# MainBoard_Simple.net
KiCad netlist of a schematic drawn in EAGLE
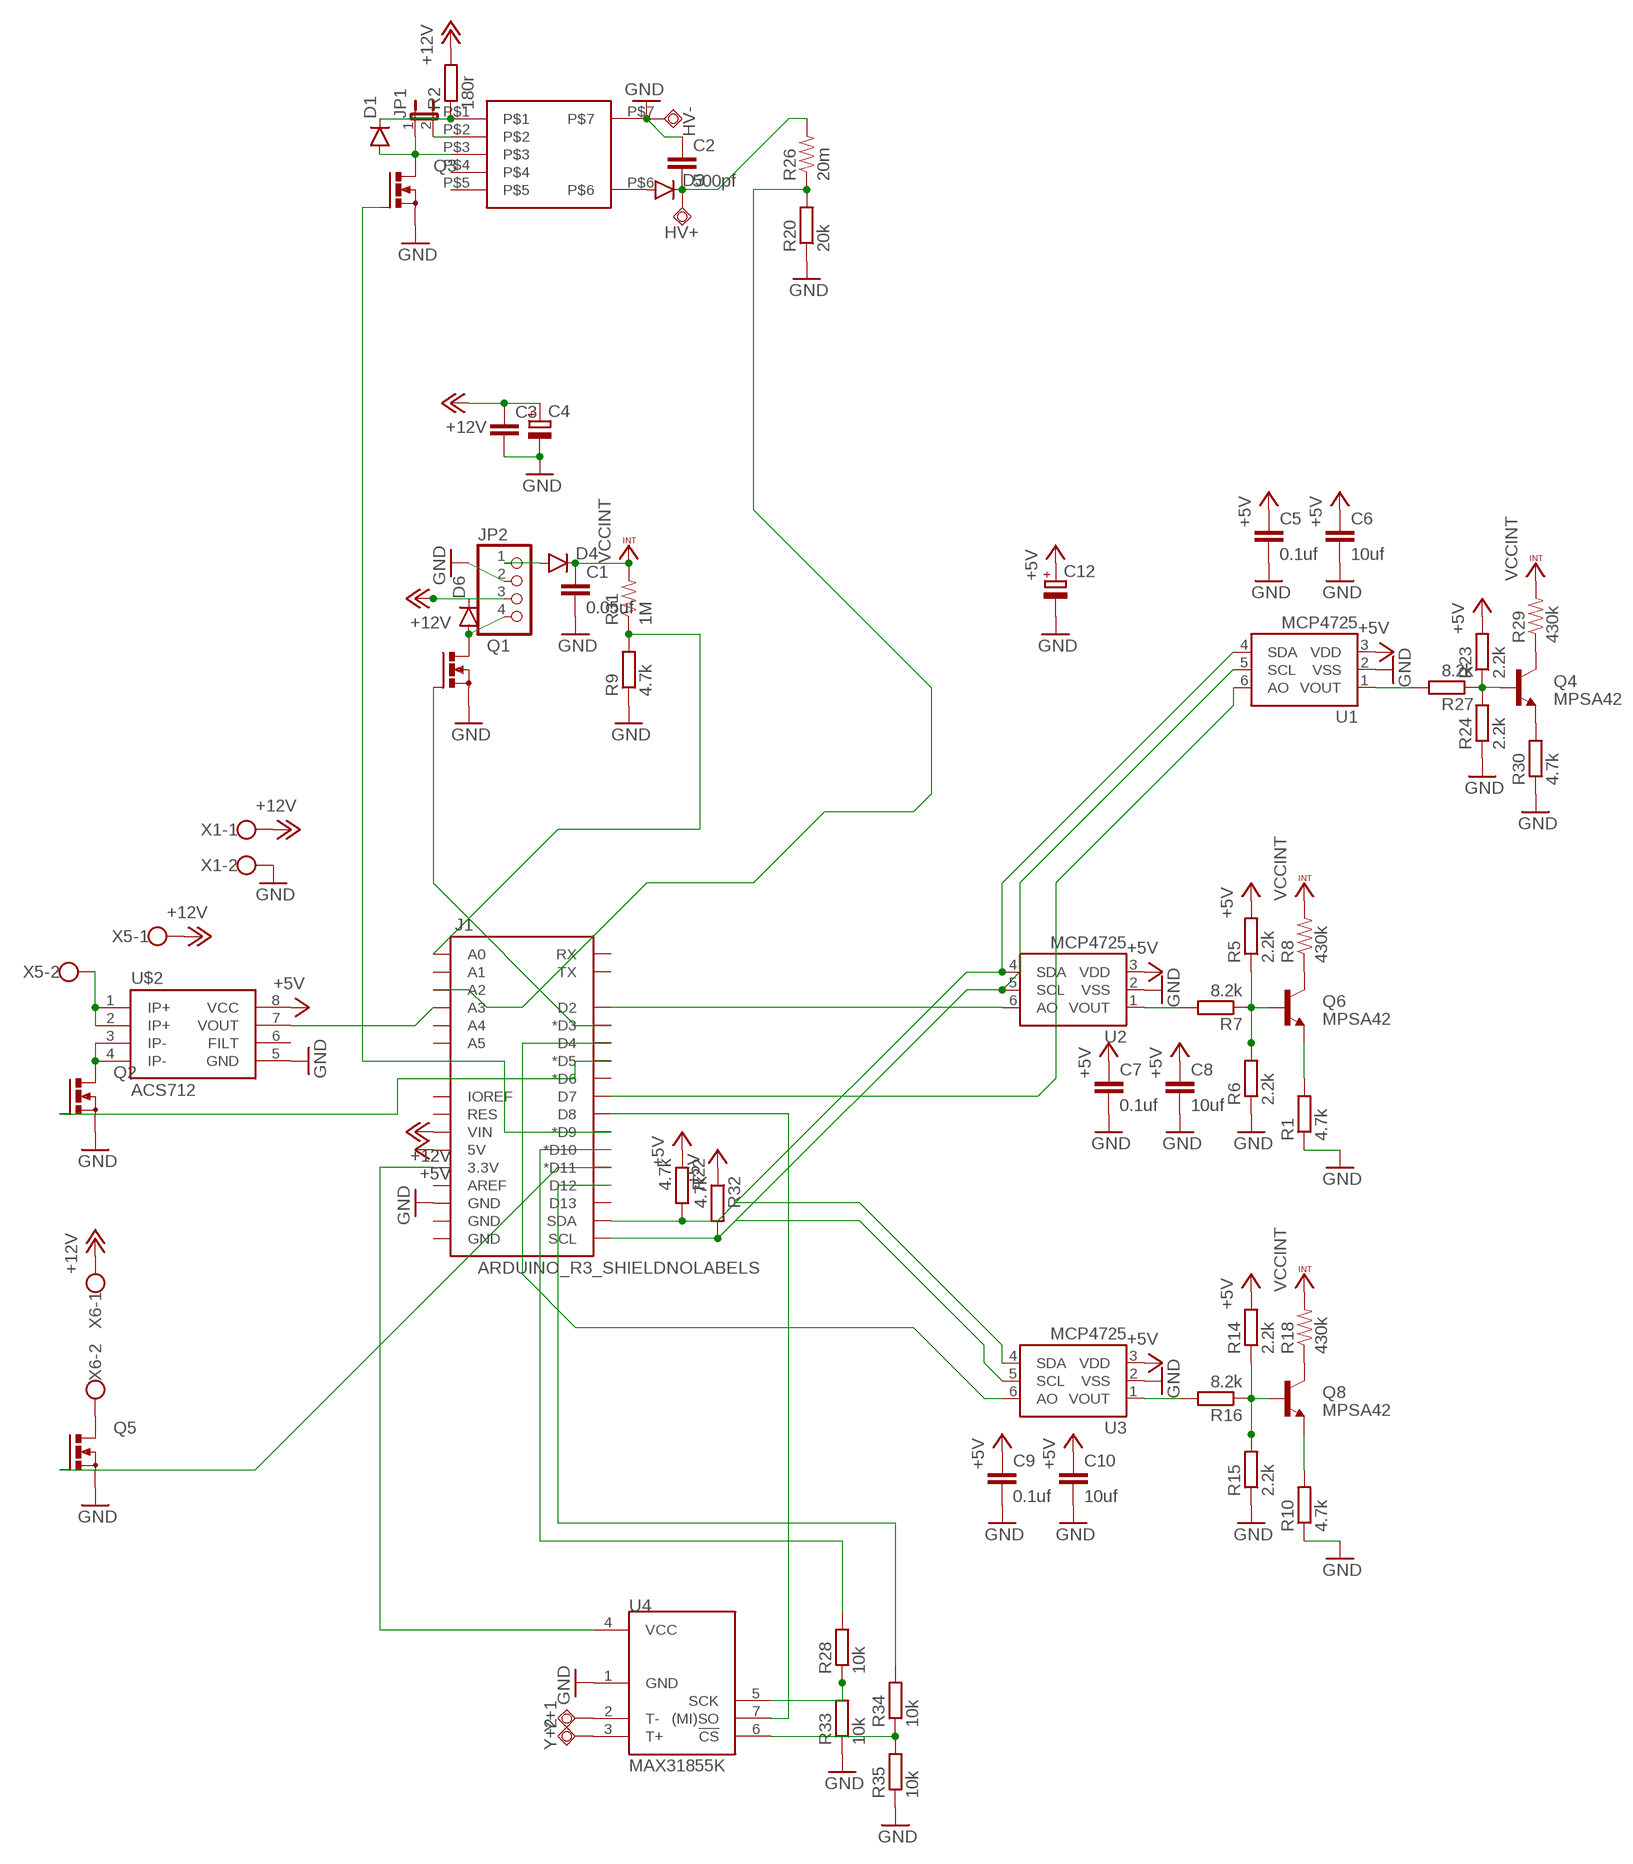
[diagram p0: schematic, sheet 1]

(export (version "E")
  (design (tool "Eeschema 10.0.6"))
  (components
    (comp (ref "C1")
      (value "0.05uf")
      (footprint "eagle-import:C1206")
      (libsource (lib "eagle-import") (part "CC1206"))
    )
    (comp (ref "C2")
      (value "500pf")
      (footprint "eagle-import:C1206")
      (libsource (lib "eagle-import") (part "CC1206"))
    )
    (comp (ref "C3")
      (value "C-EUC0603")
      (footprint "eagle-import:C0603")
      (libsource (lib "eagle-import") (part "C-EUC0603"))
    )
    (comp (ref "C4")
      (value "CPOL-EUTAP5-60")
      (footprint "eagle-import:TAP5-60")
      (libsource (lib "eagle-import") (part "CPOL-EUTAP5-60"))
    )
    (comp (ref "C5")
      (value "0.1uf")
      (footprint "eagle-import:C0603")
      (libsource (lib "eagle-import") (part "C-EUC0603"))
    )
    (comp (ref "C6")
      (value "10uf")
      (footprint "eagle-import:C0603")
      (libsource (lib "eagle-import") (part "C-EUC0603"))
    )
    (comp (ref "C7")
      (value "0.1uf")
      (footprint "eagle-import:C0603")
      (libsource (lib "eagle-import") (part "C-EUC0603"))
    )
    (comp (ref "C8")
      (value "10uf")
      (footprint "eagle-import:C0603")
      (libsource (lib "eagle-import") (part "C-EUC0603"))
    )
    (comp (ref "C9")
      (value "0.1uf")
      (footprint "eagle-import:C0603")
      (libsource (lib "eagle-import") (part "C-EUC0603"))
    )
    (comp (ref "C10")
      (value "10uf")
      (footprint "eagle-import:C0603")
      (libsource (lib "eagle-import") (part "C-EUC0603"))
    )
    (comp (ref "C12")
      (value "CPOL-EUTAP5-60")
      (footprint "eagle-import:TAP5-60")
      (libsource (lib "eagle-import") (part "CPOL-EUTAP5-60"))
    )
    (comp (ref "D1")
      (value "DIODESOD123")
      (footprint "eagle-import:SOD-123")
      (libsource (lib "eagle-import") (part "DIODESOD123"))
    )
    (comp (ref "D3")
      (value "DIODEPTH")
      (footprint "eagle-import:DIODE-1N4001")
      (libsource (lib "eagle-import") (part "DIODEPTH"))
    )
    (comp (ref "D4")
      (value "DIODESOD123")
      (footprint "eagle-import:SOD-123")
      (libsource (lib "eagle-import") (part "DIODESOD123"))
    )
    (comp (ref "D6")
      (value "DIODESOD123")
      (footprint "eagle-import:SOD-123")
      (libsource (lib "eagle-import") (part "DIODESOD123"))
    )
    (comp (ref "HV+")
      (value "TPSQPAD1-13")
      (footprint "eagle-import:P1-13")
      (libsource (lib "eagle-import") (part "TPSQPAD1-13"))
    )
    (comp (ref "HV-")
      (value "TPSQPAD1-13")
      (footprint "eagle-import:P1-13")
      (libsource (lib "eagle-import") (part "TPSQPAD1-13"))
    )
    (comp (ref "J1")
      (value "ARDUINO_R3_SHIELDNOLABELS")
      (footprint "eagle-import:UNO_R3_SHIELD_NOLABELS")
      (libsource (lib "eagle-import") (part "ARDUINO_R3_SHIELDNOLABELS"))
    )
    (comp (ref "JP1")
      (value "JUMPER-2SMD-NO")
      (footprint "eagle-import:SJ_2S-NO")
      (libsource (lib "eagle-import") (part "JUMPER-2SMD-NO"))
    )
    (comp (ref "JP2")
      (value "PINHD-1X4")
      (footprint "eagle-import:1X04")
      (libsource (lib "eagle-import") (part "PINHD-1X4"))
    )
    (comp (ref "Q1")
      (value "N-MOSFET-SO8S")
      (footprint "eagle-import:SO-08")
      (libsource (lib "eagle-import") (part "N-MOSFET-SO8S"))
    )
    (comp (ref "Q2")
      (value "N-MOSFET-SO8S")
      (footprint "eagle-import:SO-08")
      (libsource (lib "eagle-import") (part "N-MOSFET-SO8S"))
    )
    (comp (ref "Q3")
      (value "N-MOSFET-SO8S")
      (footprint "eagle-import:SO-08")
      (libsource (lib "eagle-import") (part "N-MOSFET-SO8S"))
    )
    (comp (ref "Q4")
      (value "MPSA42")
      (footprint "eagle-import:SOT23-3")
      (libsource (lib "eagle-import") (part "TRANSISTOR_NPNMPSA42"))
    )
    (comp (ref "Q5")
      (value "N-MOSFET-SO8S")
      (footprint "eagle-import:SO-08")
      (libsource (lib "eagle-import") (part "N-MOSFET-SO8S"))
    )
    (comp (ref "Q6")
      (value "MPSA42")
      (footprint "eagle-import:SOT23-3")
      (libsource (lib "eagle-import") (part "TRANSISTOR_NPNMPSA42"))
    )
    (comp (ref "Q8")
      (value "MPSA42")
      (footprint "eagle-import:SOT23-3")
      (libsource (lib "eagle-import") (part "TRANSISTOR_NPNMPSA42"))
    )
    (comp (ref "R1")
      (value "4.7k")
      (footprint "eagle-import:R0603")
      (libsource (lib "eagle-import") (part "R-EU_R0603"))
    )
    (comp (ref "R2")
      (value "180r")
      (footprint "eagle-import:R0603")
      (libsource (lib "eagle-import") (part "R-EU_R0603"))
    )
    (comp (ref "R5")
      (value "2.2k")
      (footprint "eagle-import:R0603")
      (libsource (lib "eagle-import") (part "R-EU_R0603"))
    )
    (comp (ref "R6")
      (value "2.2k")
      (footprint "eagle-import:R0603")
      (libsource (lib "eagle-import") (part "R-EU_R0603"))
    )
    (comp (ref "R7")
      (value "8.2k")
      (footprint "eagle-import:R0603")
      (libsource (lib "eagle-import") (part "R-EU_R0603"))
    )
    (comp (ref "R8")
      (value "430k")
      (footprint "eagle-import:1206")
      (libsource (lib "eagle-import") (part "RESISTOR1206"))
    )
    (comp (ref "R9")
      (value "4.7k")
      (footprint "eagle-import:R0603")
      (libsource (lib "eagle-import") (part "R-EU_R0603"))
    )
    (comp (ref "R10")
      (value "4.7k")
      (footprint "eagle-import:R0603")
      (libsource (lib "eagle-import") (part "R-EU_R0603"))
    )
    (comp (ref "R14")
      (value "2.2k")
      (footprint "eagle-import:R0603")
      (libsource (lib "eagle-import") (part "R-EU_R0603"))
    )
    (comp (ref "R15")
      (value "2.2k")
      (footprint "eagle-import:R0603")
      (libsource (lib "eagle-import") (part "R-EU_R0603"))
    )
    (comp (ref "R16")
      (value "8.2k")
      (footprint "eagle-import:R0603")
      (libsource (lib "eagle-import") (part "R-EU_R0603"))
    )
    (comp (ref "R18")
      (value "430k")
      (footprint "eagle-import:1206")
      (libsource (lib "eagle-import") (part "RESISTOR1206"))
    )
    (comp (ref "R20")
      (value "20k")
      (footprint "eagle-import:R0603")
      (libsource (lib "eagle-import") (part "R-EU_R0603"))
    )
    (comp (ref "R22")
      (value "4.7k")
      (footprint "eagle-import:R0603")
      (libsource (lib "eagle-import") (part "R-EU_R0603"))
    )
    (comp (ref "R23")
      (value "2.2k")
      (footprint "eagle-import:R0603")
      (libsource (lib "eagle-import") (part "R-EU_R0603"))
    )
    (comp (ref "R24")
      (value "2.2k")
      (footprint "eagle-import:R0603")
      (libsource (lib "eagle-import") (part "R-EU_R0603"))
    )
    (comp (ref "R26")
      (value "20m")
      (footprint "eagle-import:AXIAL-0.4")
      (libsource (lib "eagle-import") (part "RESISTORPTH-1/4W"))
    )
    (comp (ref "R27")
      (value "8.2k")
      (footprint "eagle-import:R0603")
      (libsource (lib "eagle-import") (part "R-EU_R0603"))
    )
    (comp (ref "R28")
      (value "10k")
      (footprint "eagle-import:R0603")
      (libsource (lib "eagle-import") (part "R-EU_R0603"))
    )
    (comp (ref "R29")
      (value "430k")
      (footprint "eagle-import:1206")
      (libsource (lib "eagle-import") (part "RESISTOR1206"))
    )
    (comp (ref "R30")
      (value "4.7k")
      (footprint "eagle-import:R0603")
      (libsource (lib "eagle-import") (part "R-EU_R0603"))
    )
    (comp (ref "R31")
      (value "1M")
      (footprint "eagle-import:1206")
      (libsource (lib "eagle-import") (part "RESISTOR1206"))
    )
    (comp (ref "R32")
      (value "4.7k")
      (footprint "eagle-import:R0603")
      (libsource (lib "eagle-import") (part "R-EU_R0603"))
    )
    (comp (ref "R33")
      (value "10k")
      (footprint "eagle-import:R0603")
      (libsource (lib "eagle-import") (part "R-EU_R0603"))
    )
    (comp (ref "R34")
      (value "10k")
      (footprint "eagle-import:R0603")
      (libsource (lib "eagle-import") (part "R-EU_R0603"))
    )
    (comp (ref "R35")
      (value "10k")
      (footprint "eagle-import:R0603")
      (libsource (lib "eagle-import") (part "R-EU_R0603"))
    )
    (comp (ref "U$2")
      (value "ACS712")
      (footprint "eagle-import:SO08")
      (libsource (lib "eagle-import") (part "ACS712"))
    )
    (comp (ref "U$3")
      (value "CTX")
      (footprint "eagle-import:CTX")
      (libsource (lib "eagle-import") (part "CTX"))
    )
    (comp (ref "U1")
      (value "MCP4725")
      (footprint "eagle-import:SOT23-6")
      (libsource (lib "eagle-import") (part "MCP4725SOT-23"))
    )
    (comp (ref "U2")
      (value "MCP4725")
      (footprint "eagle-import:SOT23-6")
      (libsource (lib "eagle-import") (part "MCP4725SOT-23"))
    )
    (comp (ref "U3")
      (value "MCP4725")
      (footprint "eagle-import:SOT23-6")
      (libsource (lib "eagle-import") (part "MCP4725SOT-23"))
    )
    (comp (ref "U4")
      (value "MAX31855K")
      (footprint "eagle-import:SOIC8")
      (libsource (lib "eagle-import") (part "MAX31855K"))
    )
    (comp (ref "X1")
      (value "W237-102")
      (footprint "eagle-import:W237-102")
      (fields (field (name "MPN") "237-102"))
      (libsource (lib "eagle-import") (part "W237-102"))
    )
    (comp (ref "X5")
      (value "W237-102")
      (footprint "eagle-import:W237-102")
      (fields (field (name "MPN") "237-102"))
      (libsource (lib "eagle-import") (part "W237-102"))
    )
    (comp (ref "X6")
      (value "W237-102")
      (footprint "eagle-import:W237-102")
      (fields (field (name "MPN") "237-102"))
      (libsource (lib "eagle-import") (part "W237-102"))
    )
    (comp (ref "Y+1")
      (value "TPSQPAD1-13")
      (footprint "eagle-import:P1-13")
      (libsource (lib "eagle-import") (part "TPSQPAD1-13"))
    )
    (comp (ref "Y+2")
      (value "TPSQPAD1-13")
      (footprint "eagle-import:P1-13")
      (libsource (lib "eagle-import") (part "TPSQPAD1-13"))
    )
  )
  (nets
    (net (code "1") (name "+5V") (class "Default")
      (node (ref "C10") (pin "1") (pinfunction "1_1") (pintype "passive"))
      (node (ref "C12") (pin "+") (pinfunction "+_+") (pintype "passive"))
      (node (ref "C5") (pin "1") (pinfunction "1_1") (pintype "passive"))
      (node (ref "C6") (pin "1") (pinfunction "1_1") (pintype "passive"))
      (node (ref "C7") (pin "1") (pinfunction "1_1") (pintype "passive"))
      (node (ref "C8") (pin "1") (pinfunction "1_1") (pintype "passive"))
      (node (ref "C9") (pin "1") (pinfunction "1_1") (pintype "passive"))
      (node (ref "J1") (pin "5V") (pinfunction "5V_5V") (pintype "bidirectional"))
      (node (ref "R14") (pin "2") (pinfunction "2_2") (pintype "passive"))
      (node (ref "R22") (pin "1") (pinfunction "1_1") (pintype "passive"))
      (node (ref "R23") (pin "2") (pinfunction "2_2") (pintype "passive"))
      (node (ref "R32") (pin "1") (pinfunction "1_1") (pintype "passive"))
      (node (ref "R5") (pin "2") (pinfunction "2_2") (pintype "passive"))
      (node (ref "U$2") (pin "8") (pinfunction "VCC_8") (pintype "bidirectional"))
      (node (ref "U1") (pin "3") (pinfunction "VDD_3") (pintype "bidirectional"))
      (node (ref "U2") (pin "3") (pinfunction "VDD_3") (pintype "bidirectional"))
      (node (ref "U3") (pin "3") (pinfunction "VDD_3") (pintype "bidirectional"))
    )
    (net (code "2") (name "+12V") (class "Default")
      (node (ref "C3") (pin "1") (pinfunction "1_1") (pintype "passive"))
      (node (ref "C4") (pin "+") (pinfunction "+_+") (pintype "passive"))
      (node (ref "D6") (pin "C") (pinfunction "C_C") (pintype "passive"))
      (node (ref "J1") (pin "VIN") (pinfunction "VIN_VIN") (pintype "bidirectional"))
      (node (ref "JP2") (pin "3") (pinfunction "3_3") (pintype "passive"))
      (node (ref "R2") (pin "2") (pinfunction "2_2") (pintype "passive"))
      (node (ref "X1") (pin "1") (pinfunction "KL_1") (pintype "passive"))
      (node (ref "X5") (pin "1") (pinfunction "KL_1") (pintype "passive"))
      (node (ref "X6") (pin "1") (pinfunction "KL_1") (pintype "passive"))
    )
    (net (code "3") (name "GND") (class "Default")
      (node (ref "C1") (pin "2") (pinfunction "2_2") (pintype "passive"))
      (node (ref "C10") (pin "2") (pinfunction "2_2") (pintype "passive"))
      (node (ref "C12") (pin "-") (pinfunction "-_-") (pintype "passive"))
      (node (ref "C2") (pin "1") (pinfunction "1_1") (pintype "passive"))
      (node (ref "C3") (pin "2") (pinfunction "2_2") (pintype "passive"))
      (node (ref "C4") (pin "-") (pinfunction "-_-") (pintype "passive"))
      (node (ref "C5") (pin "2") (pinfunction "2_2") (pintype "passive"))
      (node (ref "C6") (pin "2") (pinfunction "2_2") (pintype "passive"))
      (node (ref "C7") (pin "2") (pinfunction "2_2") (pintype "passive"))
      (node (ref "C8") (pin "2") (pinfunction "2_2") (pintype "passive"))
      (node (ref "C9") (pin "2") (pinfunction "2_2") (pintype "passive"))
      (node (ref "HV-") (pin "TP") (pinfunction "TP_TP") (pintype "input"))
      (node (ref "J1") (pin "GND@2") (pinfunction "GND_GND@2") (pintype "bidirectional"))
      (node (ref "JP2") (pin "2") (pinfunction "2_2") (pintype "passive"))
      (node (ref "Q1") (pin "1") (pinfunction "S_1") (pintype "passive"))
      (node (ref "Q1") (pin "2") (pinfunction "S_2") (pintype "passive"))
      (node (ref "Q1") (pin "3") (pinfunction "S_3") (pintype "passive"))
      (node (ref "Q2") (pin "1") (pinfunction "S_1") (pintype "passive"))
      (node (ref "Q2") (pin "2") (pinfunction "S_2") (pintype "passive"))
      (node (ref "Q2") (pin "3") (pinfunction "S_3") (pintype "passive"))
      (node (ref "Q3") (pin "1") (pinfunction "S_1") (pintype "passive"))
      (node (ref "Q3") (pin "2") (pinfunction "S_2") (pintype "passive"))
      (node (ref "Q3") (pin "3") (pinfunction "S_3") (pintype "passive"))
      (node (ref "Q5") (pin "1") (pinfunction "S_1") (pintype "passive"))
      (node (ref "Q5") (pin "2") (pinfunction "S_2") (pintype "passive"))
      (node (ref "Q5") (pin "3") (pinfunction "S_3") (pintype "passive"))
      (node (ref "R1") (pin "1") (pinfunction "1_1") (pintype "passive"))
      (node (ref "R10") (pin "1") (pinfunction "1_1") (pintype "passive"))
      (node (ref "R15") (pin "1") (pinfunction "1_1") (pintype "passive"))
      (node (ref "R20") (pin "1") (pinfunction "1_1") (pintype "passive"))
      (node (ref "R24") (pin "1") (pinfunction "1_1") (pintype "passive"))
      (node (ref "R30") (pin "1") (pinfunction "1_1") (pintype "passive"))
      (node (ref "R33") (pin "1") (pinfunction "1_1") (pintype "passive"))
      (node (ref "R35") (pin "1") (pinfunction "1_1") (pintype "passive"))
      (node (ref "R6") (pin "1") (pinfunction "1_1") (pintype "passive"))
      (node (ref "R9") (pin "1") (pinfunction "1_1") (pintype "passive"))
      (node (ref "U$2") (pin "5") (pinfunction "GND_5") (pintype "bidirectional"))
      (node (ref "U$3") (pin "P$7") (pinfunction "P$7_P$7") (pintype "bidirectional"))
      (node (ref "U1") (pin "2") (pinfunction "VSS_2") (pintype "bidirectional"))
      (node (ref "U2") (pin "2") (pinfunction "VSS_2") (pintype "bidirectional"))
      (node (ref "U3") (pin "2") (pinfunction "VSS_2") (pintype "bidirectional"))
      (node (ref "U4") (pin "1") (pinfunction "GND_1") (pintype "bidirectional"))
      (node (ref "X1") (pin "2") (pinfunction "KL_2") (pintype "passive"))
    )
    (net (code "4") (name "Net-(D1-PadA)") (class "Default")
      (node (ref "D1") (pin "A") (pinfunction "A_A") (pintype "passive"))
      (node (ref "JP1") (pin "1") (pinfunction "1_1") (pintype "passive"))
      (node (ref "Q3") (pin "5") (pinfunction "D_5") (pintype "passive"))
      (node (ref "Q3") (pin "6") (pinfunction "D_6") (pintype "passive"))
      (node (ref "Q3") (pin "7") (pinfunction "D_7") (pintype "passive"))
      (node (ref "Q3") (pin "8") (pinfunction "D_8") (pintype "passive"))
      (node (ref "U$3") (pin "P$3") (pinfunction "P$3_P$3") (pintype "bidirectional"))
    )
    (net (code "5") (name "Net-(D1-PadC)") (class "Default")
      (node (ref "D1") (pin "C") (pinfunction "C_C") (pintype "passive"))
      (node (ref "R2") (pin "1") (pinfunction "1_1") (pintype "passive"))
      (node (ref "U$3") (pin "P$1") (pinfunction "P$1_P$1") (pintype "bidirectional"))
    )
    (net (code "6") (name "Net-(D3-PadA)") (class "Default")
      (node (ref "D3") (pin "A") (pinfunction "A_A") (pintype "passive"))
      (node (ref "U$3") (pin "P$6") (pinfunction "P$6_P$6") (pintype "bidirectional"))
    )
    (net (code "7") (name "Net-(D4-PadA)") (class "Default")
      (node (ref "D4") (pin "A") (pinfunction "A_A") (pintype "passive"))
      (node (ref "JP2") (pin "1") (pinfunction "1_1") (pintype "passive"))
    )
    (net (code "8") (name "Net-(D6-PadA)") (class "Default")
      (node (ref "D6") (pin "A") (pinfunction "A_A") (pintype "passive"))
      (node (ref "JP2") (pin "4") (pinfunction "4_4") (pintype "passive"))
      (node (ref "Q1") (pin "5") (pinfunction "D_5") (pintype "passive"))
      (node (ref "Q1") (pin "6") (pinfunction "D_6") (pintype "passive"))
      (node (ref "Q1") (pin "7") (pinfunction "D_7") (pintype "passive"))
      (node (ref "Q1") (pin "8") (pinfunction "D_8") (pintype "passive"))
    )
    (net (code "9") (name "Net-(J1-*D3)") (class "Default")
      (node (ref "J1") (pin "D3") (pinfunction "*D3_D3") (pintype "bidirectional"))
      (node (ref "Q1") (pin "4") (pinfunction "G_4") (pintype "passive"))
    )
    (net (code "10") (name "Net-(J1-*D5)") (class "Default")
      (node (ref "J1") (pin "D5") (pinfunction "*D5_D5") (pintype "bidirectional"))
      (node (ref "Q2") (pin "4") (pinfunction "G_4") (pintype "passive"))
    )
    (net (code "11") (name "Net-(J1-*D9)") (class "Default")
      (node (ref "J1") (pin "D9") (pinfunction "*D9_D9") (pintype "bidirectional"))
      (node (ref "Q3") (pin "4") (pinfunction "G_4") (pintype "passive"))
    )
    (net (code "12") (name "Net-(J1-*D10)") (class "Default")
      (node (ref "J1") (pin "D10") (pinfunction "*D10_D10") (pintype "bidirectional"))
      (node (ref "R28") (pin "2") (pinfunction "2_2") (pintype "passive"))
    )
    (net (code "13") (name "Net-(J1-*D11)") (class "Default")
      (node (ref "J1") (pin "D11") (pinfunction "*D11_D11") (pintype "bidirectional"))
      (node (ref "Q5") (pin "4") (pinfunction "G_4") (pintype "passive"))
    )
    (net (code "14") (name "Net-(J1-PadA0)") (class "Default")
      (node (ref "J1") (pin "A0") (pinfunction "A0_A0") (pintype "bidirectional"))
      (node (ref "R31") (pin "1") (pinfunction "1_1") (pintype "passive"))
      (node (ref "R9") (pin "2") (pinfunction "2_2") (pintype "passive"))
    )
    (net (code "15") (name "Net-(J1-PadD12)") (class "Default")
      (node (ref "J1") (pin "D12") (pinfunction "D12_D12") (pintype "bidirectional"))
      (node (ref "R34") (pin "2") (pinfunction "2_2") (pintype "passive"))
    )
    (net (code "16") (name "Net-(JP1-Pad2)") (class "Default")
      (node (ref "JP1") (pin "2") (pinfunction "2_2") (pintype "passive"))
      (node (ref "U$3") (pin "P$2") (pinfunction "P$2_P$2") (pintype "bidirectional"))
    )
    (net (code "17") (name "Net-(Q2-D-Pad5)") (class "Default")
      (node (ref "Q2") (pin "5") (pinfunction "D_5") (pintype "passive"))
      (node (ref "Q2") (pin "6") (pinfunction "D_6") (pintype "passive"))
      (node (ref "Q2") (pin "7") (pinfunction "D_7") (pintype "passive"))
      (node (ref "Q2") (pin "8") (pinfunction "D_8") (pintype "passive"))
      (node (ref "U$2") (pin "3") (pinfunction "IP-_3") (pintype "bidirectional"))
      (node (ref "U$2") (pin "4") (pinfunction "IP-_4") (pintype "bidirectional"))
    )
    (net (code "18") (name "Net-(Q4-B)") (class "Default")
      (node (ref "Q4") (pin "1") (pinfunction "B_1") (pintype "passive"))
      (node (ref "R23") (pin "1") (pinfunction "1_1") (pintype "passive"))
      (node (ref "R24") (pin "2") (pinfunction "2_2") (pintype "passive"))
      (node (ref "R27") (pin "1") (pinfunction "1_1") (pintype "passive"))
    )
    (net (code "19") (name "Net-(Q4-C)") (class "Default")
      (node (ref "Q4") (pin "3") (pinfunction "C_3") (pintype "passive"))
      (node (ref "R29") (pin "1") (pinfunction "1_1") (pintype "passive"))
    )
    (net (code "20") (name "Net-(Q4-E)") (class "Default")
      (node (ref "Q4") (pin "2") (pinfunction "E_2") (pintype "passive"))
      (node (ref "R30") (pin "2") (pinfunction "2_2") (pintype "passive"))
    )
    (net (code "21") (name "Net-(Q6-B)") (class "Default")
      (node (ref "Q6") (pin "1") (pinfunction "B_1") (pintype "passive"))
      (node (ref "R5") (pin "1") (pinfunction "1_1") (pintype "passive"))
      (node (ref "R6") (pin "2") (pinfunction "2_2") (pintype "passive"))
      (node (ref "R7") (pin "1") (pinfunction "1_1") (pintype "passive"))
    )
    (net (code "22") (name "Net-(Q6-C)") (class "Default")
      (node (ref "Q6") (pin "3") (pinfunction "C_3") (pintype "passive"))
      (node (ref "R8") (pin "1") (pinfunction "1_1") (pintype "passive"))
    )
    (net (code "23") (name "Net-(Q6-E)") (class "Default")
      (node (ref "Q6") (pin "2") (pinfunction "E_2") (pintype "passive"))
      (node (ref "R1") (pin "2") (pinfunction "2_2") (pintype "passive"))
    )
    (net (code "24") (name "Net-(Q8-B)") (class "Default")
      (node (ref "Q8") (pin "1") (pinfunction "B_1") (pintype "passive"))
      (node (ref "R14") (pin "1") (pinfunction "1_1") (pintype "passive"))
      (node (ref "R15") (pin "2") (pinfunction "2_2") (pintype "passive"))
      (node (ref "R16") (pin "1") (pinfunction "1_1") (pintype "passive"))
    )
    (net (code "25") (name "Net-(Q8-C)") (class "Default")
      (node (ref "Q8") (pin "3") (pinfunction "C_3") (pintype "passive"))
      (node (ref "R18") (pin "1") (pinfunction "1_1") (pintype "passive"))
    )
    (net (code "26") (name "Net-(Q8-E)") (class "Default")
      (node (ref "Q8") (pin "2") (pinfunction "E_2") (pintype "passive"))
      (node (ref "R10") (pin "2") (pinfunction "2_2") (pintype "passive"))
    )
    (net (code "27") (name "Net-(R26-1)") (class "Default")
      (node (ref "J1") (pin "A2") (pinfunction "A2_A2") (pintype "bidirectional"))
      (node (ref "R20") (pin "2") (pinfunction "2_2") (pintype "passive"))
      (node (ref "R26") (pin "P$1") (pinfunction "1_P$1") (pintype "passive"))
    )
    (net (code "28") (name "Net-(R26-2)") (class "Default")
      (node (ref "C2") (pin "2") (pinfunction "2_2") (pintype "passive"))
      (node (ref "D3") (pin "C") (pinfunction "C_C") (pintype "passive"))
      (node (ref "HV+") (pin "TP") (pinfunction "TP_TP") (pintype "input"))
      (node (ref "R26") (pin "P$2") (pinfunction "2_P$2") (pintype "passive"))
    )
    (net (code "29") (name "Net-(U$2-VOUT)") (class "Default")
      (node (ref "J1") (pin "A3") (pinfunction "A3_A3") (pintype "bidirectional"))
      (node (ref "U$2") (pin "7") (pinfunction "VOUT_7") (pintype "bidirectional"))
    )
    (net (code "30") (name "Net-(U1-AO)") (class "Default")
      (node (ref "J1") (pin "D7") (pinfunction "D7_D7") (pintype "bidirectional"))
      (node (ref "U1") (pin "6") (pinfunction "AO_6") (pintype "bidirectional"))
    )
    (net (code "31") (name "Net-(U1-SCL)") (class "Default")
      (node (ref "J1") (pin "SCL") (pinfunction "SCL_SCL") (pintype "bidirectional"))
      (node (ref "R32") (pin "2") (pinfunction "2_2") (pintype "passive"))
      (node (ref "U1") (pin "5") (pinfunction "SCL_5") (pintype "bidirectional"))
      (node (ref "U2") (pin "5") (pinfunction "SCL_5") (pintype "bidirectional"))
      (node (ref "U3") (pin "5") (pinfunction "SCL_5") (pintype "bidirectional"))
    )
    (net (code "32") (name "Net-(U1-SDA)") (class "Default")
      (node (ref "J1") (pin "SDA") (pinfunction "SDA_SDA") (pintype "bidirectional"))
      (node (ref "R22") (pin "2") (pinfunction "2_2") (pintype "passive"))
      (node (ref "U1") (pin "4") (pinfunction "SDA_4") (pintype "bidirectional"))
      (node (ref "U2") (pin "4") (pinfunction "SDA_4") (pintype "bidirectional"))
      (node (ref "U3") (pin "4") (pinfunction "SDA_4") (pintype "bidirectional"))
    )
    (net (code "33") (name "Net-(U1-VOUT)") (class "Default")
      (node (ref "R27") (pin "2") (pinfunction "2_2") (pintype "passive"))
      (node (ref "U1") (pin "1") (pinfunction "VOUT_1") (pintype "bidirectional"))
    )
    (net (code "34") (name "Net-(U2-AO)") (class "Default")
      (node (ref "J1") (pin "D2") (pinfunction "D2_D2") (pintype "bidirectional"))
      (node (ref "U2") (pin "6") (pinfunction "AO_6") (pintype "bidirectional"))
    )
    (net (code "35") (name "Net-(U2-VOUT)") (class "Default")
      (node (ref "R7") (pin "2") (pinfunction "2_2") (pintype "passive"))
      (node (ref "U2") (pin "1") (pinfunction "VOUT_1") (pintype "bidirectional"))
    )
    (net (code "36") (name "Net-(U3-AO)") (class "Default")
      (node (ref "J1") (pin "D4") (pinfunction "D4_D4") (pintype "bidirectional"))
      (node (ref "U3") (pin "6") (pinfunction "AO_6") (pintype "bidirectional"))
    )
    (net (code "37") (name "Net-(U3-VOUT)") (class "Default")
      (node (ref "R16") (pin "2") (pinfunction "2_2") (pintype "passive"))
      (node (ref "U3") (pin "1") (pinfunction "VOUT_1") (pintype "bidirectional"))
    )
    (net (code "38") (name "Net-(U4-(MI)SO)") (class "Default")
      (node (ref "J1") (pin "D8") (pinfunction "D8_D8") (pintype "bidirectional"))
      (node (ref "U4") (pin "7") (pinfunction "(MI)SO_7") (pintype "bidirectional"))
    )
    (net (code "39") (name "Net-(U4-SCK)") (class "Default")
      (node (ref "R28") (pin "1") (pinfunction "1_1") (pintype "passive"))
      (node (ref "R33") (pin "2") (pinfunction "2_2") (pintype "passive"))
      (node (ref "U4") (pin "5") (pinfunction "SCK_5") (pintype "bidirectional"))
    )
    (net (code "40") (name "Net-(U4-T+)") (class "Default")
      (node (ref "U4") (pin "3") (pinfunction "T+_3") (pintype "bidirectional"))
      (node (ref "Y+2") (pin "TP") (pinfunction "TP_TP") (pintype "input"))
    )
    (net (code "41") (name "Net-(U4-T-)") (class "Default")
      (node (ref "U4") (pin "2") (pinfunction "T-_2") (pintype "bidirectional"))
      (node (ref "Y+1") (pin "TP") (pinfunction "TP_TP") (pintype "input"))
    )
    (net (code "42") (name "Net-(U4-VCC)") (class "Default")
      (node (ref "J1") (pin "3.3V") (pinfunction "3.3V_3.3V") (pintype "bidirectional"))
      (node (ref "U4") (pin "4") (pinfunction "VCC_4") (pintype "bidirectional"))
    )
    (net (code "43") (name "Net-(U4-~{CS})") (class "Default")
      (node (ref "R34") (pin "1") (pinfunction "1_1") (pintype "passive"))
      (node (ref "R35") (pin "2") (pinfunction "2_2") (pintype "passive"))
      (node (ref "U4") (pin "6") (pinfunction "~{CS}_6") (pintype "bidirectional"))
    )
    (net (code "44") (name "Net-(X5B-KL)") (class "Default")
      (node (ref "U$2") (pin "1") (pinfunction "IP+_1") (pintype "bidirectional"))
      (node (ref "U$2") (pin "2") (pinfunction "IP+_2") (pintype "bidirectional"))
      (node (ref "X5") (pin "2") (pinfunction "KL_2") (pintype "passive"))
    )
    (net (code "45") (name "Net-(X6B-KL)") (class "Default")
      (node (ref "Q5") (pin "5") (pinfunction "D_5") (pintype "passive"))
      (node (ref "Q5") (pin "6") (pinfunction "D_6") (pintype "passive"))
      (node (ref "Q5") (pin "7") (pinfunction "D_7") (pintype "passive"))
      (node (ref "Q5") (pin "8") (pinfunction "D_8") (pintype "passive"))
      (node (ref "X6") (pin "2") (pinfunction "KL_2") (pintype "passive"))
    )
    (net (code "46") (name "VCCINT") (class "Default")
      (node (ref "C1") (pin "1") (pinfunction "1_1") (pintype "passive"))
      (node (ref "D4") (pin "C") (pinfunction "C_C") (pintype "passive"))
      (node (ref "R18") (pin "2") (pinfunction "2_2") (pintype "passive"))
      (node (ref "R29") (pin "2") (pinfunction "2_2") (pintype "passive"))
      (node (ref "R31") (pin "2") (pinfunction "2_2") (pintype "passive"))
      (node (ref "R8") (pin "2") (pinfunction "2_2") (pintype "passive"))
    )
    (net (code "47") (name "unconnected-(J1-*D6-PadD6)") (class "Default")
      (node (ref "J1") (pin "D6") (pinfunction "*D6_D6") (pintype "bidirectional"))
    )
    (net (code "48") (name "unconnected-(J1-GND-PadGND@0)") (class "Default")
      (node (ref "J1") (pin "GND@0") (pinfunction "GND_GND@0") (pintype "bidirectional"))
    )
    (net (code "49") (name "unconnected-(J1-GND-PadGND@1)") (class "Default")
      (node (ref "J1") (pin "GND@1") (pinfunction "GND_GND@1") (pintype "bidirectional"))
    )
    (net (code "50") (name "unconnected-(J1-PadA1)") (class "Default")
      (node (ref "J1") (pin "A1") (pinfunction "A1_A1") (pintype "bidirectional"))
    )
    (net (code "51") (name "unconnected-(J1-PadA4)") (class "Default")
      (node (ref "J1") (pin "A4") (pinfunction "A4_A4") (pintype "bidirectional"))
    )
    (net (code "52") (name "unconnected-(J1-PadA5)") (class "Default")
      (node (ref "J1") (pin "A5") (pinfunction "A5_A5") (pintype "bidirectional"))
    )
    (net (code "53") (name "unconnected-(J1-PadAREF)") (class "Default")
      (node (ref "J1") (pin "AREF") (pinfunction "AREF_AREF") (pintype "bidirectional"))
    )
    (net (code "54") (name "unconnected-(J1-PadD13)") (class "Default")
      (node (ref "J1") (pin "D13") (pinfunction "D13_D13") (pintype "bidirectional"))
    )
    (net (code "55") (name "unconnected-(J1-PadIOREF)") (class "Default")
      (node (ref "J1") (pin "IOREF") (pinfunction "IOREF_IOREF") (pintype "bidirectional"))
    )
    (net (code "56") (name "unconnected-(J1-PadRES)") (class "Default")
      (node (ref "J1") (pin "RES") (pinfunction "RES_RES") (pintype "bidirectional"))
    )
    (net (code "57") (name "unconnected-(J1-PadRX)") (class "Default")
      (node (ref "J1") (pin "RX") (pinfunction "RX_RX") (pintype "bidirectional"))
    )
    (net (code "58") (name "unconnected-(J1-PadTX)") (class "Default")
      (node (ref "J1") (pin "TX") (pinfunction "TX_TX") (pintype "bidirectional"))
    )
    (net (code "59") (name "unconnected-(U$2-FILT-Pad6)") (class "Default")
      (node (ref "U$2") (pin "6") (pinfunction "FILT_6") (pintype "bidirectional"))
    )
    (net (code "60") (name "unconnected-(U$3-PadP$4)") (class "Default")
      (node (ref "U$3") (pin "P$4") (pinfunction "P$4_P$4") (pintype "bidirectional"))
    )
    (net (code "61") (name "unconnected-(U$3-PadP$5)") (class "Default")
      (node (ref "U$3") (pin "P$5") (pinfunction "P$5_P$5") (pintype "bidirectional"))
    )
  )
)
